# artboat_rev_a.net
KiCad netlist of a schematic drawn in EAGLE
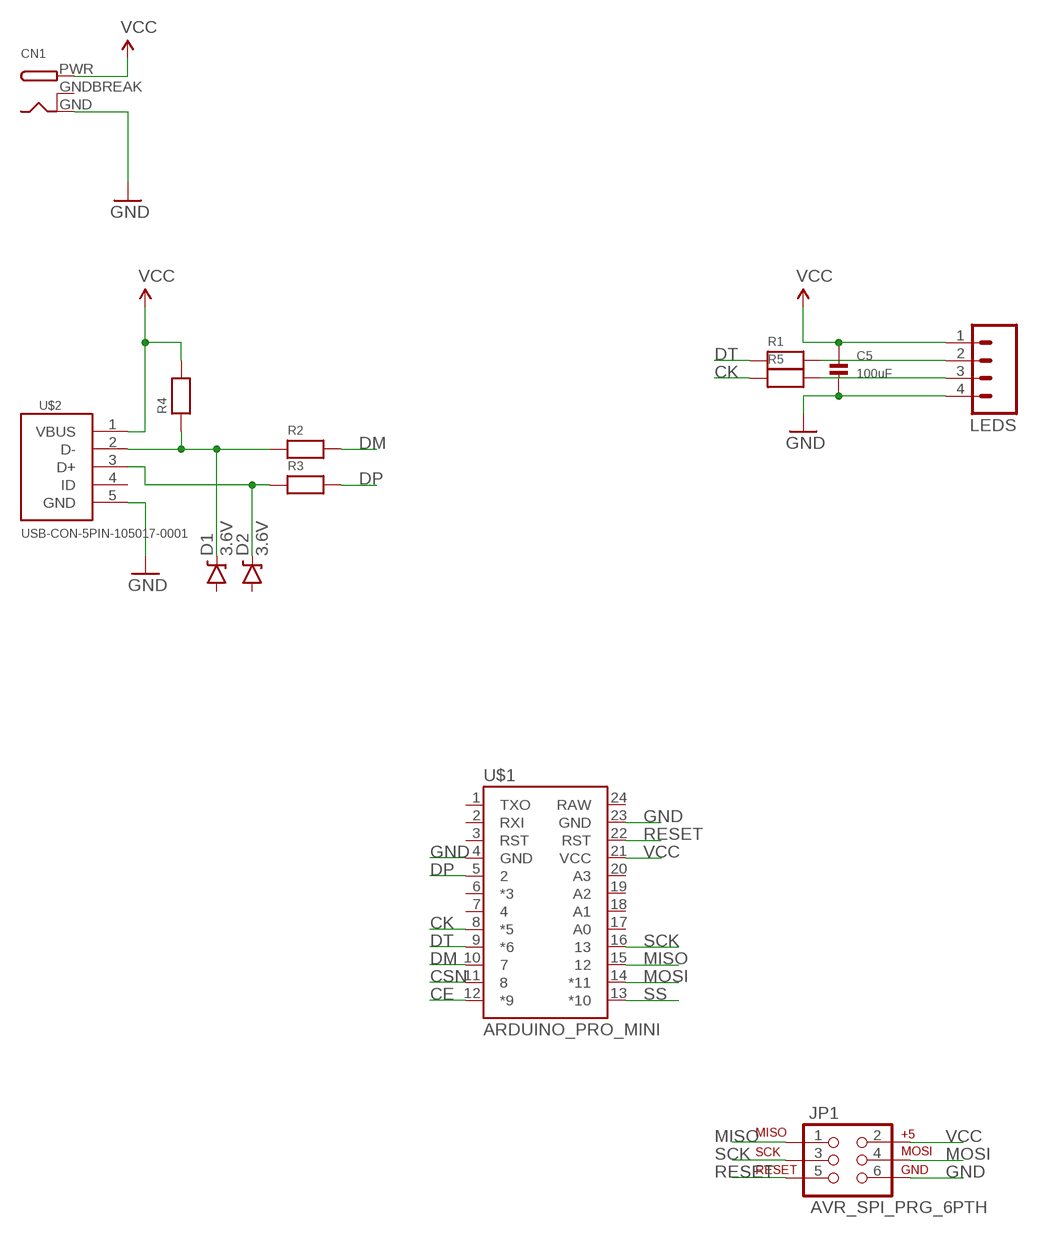
[diagram p0: schematic, sheet 1]

(export (version "E")
  (design (tool "Eeschema 10.0.6"))
  (components
    (comp (ref "C5")
      (value "100uF")
      (footprint "eagle-import:1206")
      (libsource (lib "eagle-import") (part "CAP_CERAMIC1206"))
    )
    (comp (ref "CN1")
      (value "DCBARRELPTH")
      (footprint "eagle-import:DCJACK_2MM_PTH")
      (libsource (lib "eagle-import") (part "DCBARRELPTH"))
    )
    (comp (ref "D1")
      (value "3.6V")
      (footprint "eagle-import:SOD-323")
      (libsource (lib "eagle-import") (part "DIODE-ZENER3.6V"))
    )
    (comp (ref "D2")
      (value "3.6V")
      (footprint "eagle-import:SOD-323")
      (libsource (lib "eagle-import") (part "DIODE-ZENER3.6V"))
    )
    (comp (ref "JP1")
      (value "AVR_SPI_PRG_6PTH")
      (footprint "eagle-import:2X3")
      (libsource (lib "eagle-import") (part "AVR_SPI_PRG_6PTH"))
    )
    (comp (ref "LEDS")
      (value "M04PTH")
      (footprint "eagle-import:1X04")
      (libsource (lib "eagle-import") (part "M04PTH"))
    )
    (comp (ref "R1")
      (value "RESISTOR_0603")
      (footprint "eagle-import:_0603")
      (libsource (lib "eagle-import") (part "RESISTOR_0603"))
    )
    (comp (ref "R2")
      (value "RESISTOR_0603")
      (footprint "eagle-import:_0603")
      (libsource (lib "eagle-import") (part "RESISTOR_0603"))
    )
    (comp (ref "R3")
      (value "RESISTOR_0603")
      (footprint "eagle-import:_0603")
      (libsource (lib "eagle-import") (part "RESISTOR_0603"))
    )
    (comp (ref "R4")
      (value "RESISTOR_0603")
      (footprint "eagle-import:_0603")
      (libsource (lib "eagle-import") (part "RESISTOR_0603"))
    )
    (comp (ref "R5")
      (value "RESISTOR_0603")
      (footprint "eagle-import:_0603")
      (libsource (lib "eagle-import") (part "RESISTOR_0603"))
    )
    (comp (ref "U$1")
      (value "ARDUINO_PRO_MINI")
      (footprint "eagle-import:ARDUINO_PRO_MINI")
      (libsource (lib "eagle-import") (part "ARDUINO_PRO_MINI"))
    )
    (comp (ref "U$2")
      (value "USB-CON-5PIN-105017-0001")
      (footprint "eagle-import:USB-MICRO-MOLEX-105017-0001")
      (libsource (lib "eagle-import") (part "USB-CON-5PIN-105017-0001"))
    )
  )
  (nets
    (net (code "1") (name "/CE") (class "Default")
      (node (ref "U$1") (pin "12") (pinfunction "*9_12") (pintype "bidirectional"))
    )
    (net (code "2") (name "/CK") (class "Default")
      (node (ref "R5") (pin "1") (pinfunction "1_1") (pintype "passive"))
      (node (ref "U$1") (pin "8") (pinfunction "*5_8") (pintype "bidirectional"))
    )
    (net (code "3") (name "/CSN") (class "Default")
      (node (ref "U$1") (pin "11") (pinfunction "8_11") (pintype "bidirectional"))
    )
    (net (code "4") (name "/DM") (class "Default")
      (node (ref "R2") (pin "2") (pinfunction "2_2") (pintype "passive"))
      (node (ref "U$1") (pin "10") (pinfunction "7_10") (pintype "bidirectional"))
    )
    (net (code "5") (name "/DP") (class "Default")
      (node (ref "R3") (pin "2") (pinfunction "2_2") (pintype "passive"))
      (node (ref "U$1") (pin "5") (pinfunction "2_5") (pintype "bidirectional"))
    )
    (net (code "6") (name "/DT") (class "Default")
      (node (ref "R1") (pin "1") (pinfunction "1_1") (pintype "passive"))
      (node (ref "U$1") (pin "9") (pinfunction "*6_9") (pintype "bidirectional"))
    )
    (net (code "7") (name "/GNDBREAK") (class "Default")
      (node (ref "CN1") (pin "GNDBREAK") (pinfunction "GNDBREAK_GNDBREAK") (pintype "power_in"))
    )
    (net (code "8") (name "/MISO") (class "Default")
      (node (ref "JP1") (pin "1") (pinfunction "1_1") (pintype "passive"))
      (node (ref "U$1") (pin "15") (pinfunction "12_15") (pintype "bidirectional"))
    )
    (net (code "9") (name "/MOSI") (class "Default")
      (node (ref "JP1") (pin "4") (pinfunction "4_4") (pintype "passive"))
      (node (ref "U$1") (pin "14") (pinfunction "*11_14") (pintype "bidirectional"))
    )
    (net (code "10") (name "/N$2") (class "Default")
      (node (ref "LEDS") (pin "2") (pinfunction "2_2") (pintype "passive"))
      (node (ref "LEDS") (pin "3") (pinfunction "3_3") (pintype "passive"))
      (node (ref "R1") (pin "2") (pinfunction "2_2") (pintype "passive"))
      (node (ref "R5") (pin "2") (pinfunction "2_2") (pintype "passive"))
    )
    (net (code "11") (name "/RESET") (class "Default")
      (node (ref "JP1") (pin "5") (pinfunction "5_5") (pintype "passive"))
      (node (ref "U$1") (pin "22") (pinfunction "RST_22") (pintype "bidirectional"))
    )
    (net (code "12") (name "/SCK") (class "Default")
      (node (ref "JP1") (pin "3") (pinfunction "3_3") (pintype "passive"))
      (node (ref "U$1") (pin "16") (pinfunction "13_16") (pintype "bidirectional"))
    )
    (net (code "13") (name "/SS") (class "Default")
      (node (ref "U$1") (pin "13") (pinfunction "*10_13") (pintype "bidirectional"))
    )
    (net (code "14") (name "GND") (class "Default")
      (node (ref "C5") (pin "2") (pinfunction "P$2_2") (pintype "passive"))
      (node (ref "CN1") (pin "GND") (pinfunction "GND_GND") (pintype "power_in"))
      (node (ref "JP1") (pin "6") (pinfunction "6_6") (pintype "passive"))
      (node (ref "LEDS") (pin "4") (pinfunction "4_4") (pintype "passive"))
      (node (ref "U$1") (pin "23") (pinfunction "GND_23") (pintype "bidirectional"))
      (node (ref "U$1") (pin "4") (pinfunction "GND_4") (pintype "bidirectional"))
      (node (ref "U$2") (pin "5") (pinfunction "GND_5") (pintype "power_in"))
    )
    (net (code "15") (name "Net-(U$2-D+)") (class "Default")
      (node (ref "D2") (pin "C") (pinfunction "C_C") (pintype "passive"))
      (node (ref "R3") (pin "1") (pinfunction "1_1") (pintype "passive"))
      (node (ref "U$2") (pin "3") (pinfunction "D+_3") (pintype "bidirectional"))
    )
    (net (code "16") (name "Net-(U$2-D-)") (class "Default")
      (node (ref "D1") (pin "C") (pinfunction "C_C") (pintype "passive"))
      (node (ref "R2") (pin "1") (pinfunction "1_1") (pintype "passive"))
      (node (ref "R4") (pin "1") (pinfunction "1_1") (pintype "passive"))
      (node (ref "U$2") (pin "2") (pinfunction "D-_2") (pintype "bidirectional"))
    )
    (net (code "17") (name "VCC") (class "Default")
      (node (ref "C5") (pin "1") (pinfunction "P$1_1") (pintype "passive"))
      (node (ref "CN1") (pin "PWR") (pinfunction "PWR_PWR") (pintype "power_in"))
      (node (ref "JP1") (pin "2") (pinfunction "2_2") (pintype "passive"))
      (node (ref "LEDS") (pin "1") (pinfunction "1_1") (pintype "passive"))
      (node (ref "R4") (pin "2") (pinfunction "2_2") (pintype "passive"))
      (node (ref "U$1") (pin "21") (pinfunction "VCC_21") (pintype "bidirectional"))
      (node (ref "U$2") (pin "1") (pinfunction "VBUS_1") (pintype "power_in"))
    )
    (net (code "18") (name "unconnected-(D1-PadA)") (class "Default")
      (node (ref "D1") (pin "A") (pinfunction "A_A") (pintype "passive"))
    )
    (net (code "19") (name "unconnected-(D2-PadA)") (class "Default")
      (node (ref "D2") (pin "A") (pinfunction "A_A") (pintype "passive"))
    )
    (net (code "20") (name "unconnected-(U$1-*3-Pad6)") (class "Default")
      (node (ref "U$1") (pin "6") (pinfunction "*3_6") (pintype "bidirectional"))
    )
    (net (code "21") (name "unconnected-(U$1-4-Pad7)") (class "Default")
      (node (ref "U$1") (pin "7") (pinfunction "4_7") (pintype "bidirectional"))
    )
    (net (code "22") (name "unconnected-(U$1-A0-Pad17)") (class "Default")
      (node (ref "U$1") (pin "17") (pinfunction "A0_17") (pintype "bidirectional"))
    )
    (net (code "23") (name "unconnected-(U$1-A1-Pad18)") (class "Default")
      (node (ref "U$1") (pin "18") (pinfunction "A1_18") (pintype "bidirectional"))
    )
    (net (code "24") (name "unconnected-(U$1-A2-Pad19)") (class "Default")
      (node (ref "U$1") (pin "19") (pinfunction "A2_19") (pintype "bidirectional"))
    )
    (net (code "25") (name "unconnected-(U$1-A3-Pad20)") (class "Default")
      (node (ref "U$1") (pin "20") (pinfunction "A3_20") (pintype "bidirectional"))
    )
    (net (code "26") (name "unconnected-(U$1-RAW-Pad24)") (class "Default")
      (node (ref "U$1") (pin "24") (pinfunction "RAW_24") (pintype "bidirectional"))
    )
    (net (code "27") (name "unconnected-(U$1-RST-Pad3)") (class "Default")
      (node (ref "U$1") (pin "3") (pinfunction "RST_3") (pintype "bidirectional"))
    )
    (net (code "28") (name "unconnected-(U$1-RXI-Pad2)") (class "Default")
      (node (ref "U$1") (pin "2") (pinfunction "RXI_2") (pintype "bidirectional"))
    )
    (net (code "29") (name "unconnected-(U$1-TXO-Pad1)") (class "Default")
      (node (ref "U$1") (pin "1") (pinfunction "TXO_1") (pintype "bidirectional"))
    )
    (net (code "30") (name "unconnected-(U$2-ID-Pad4)") (class "Default")
      (node (ref "U$2") (pin "4") (pinfunction "ID_4") (pintype "bidirectional"))
    )
  )
)
